# Ejercicio1.net
KiCad netlist of a schematic drawn in Altium Designer
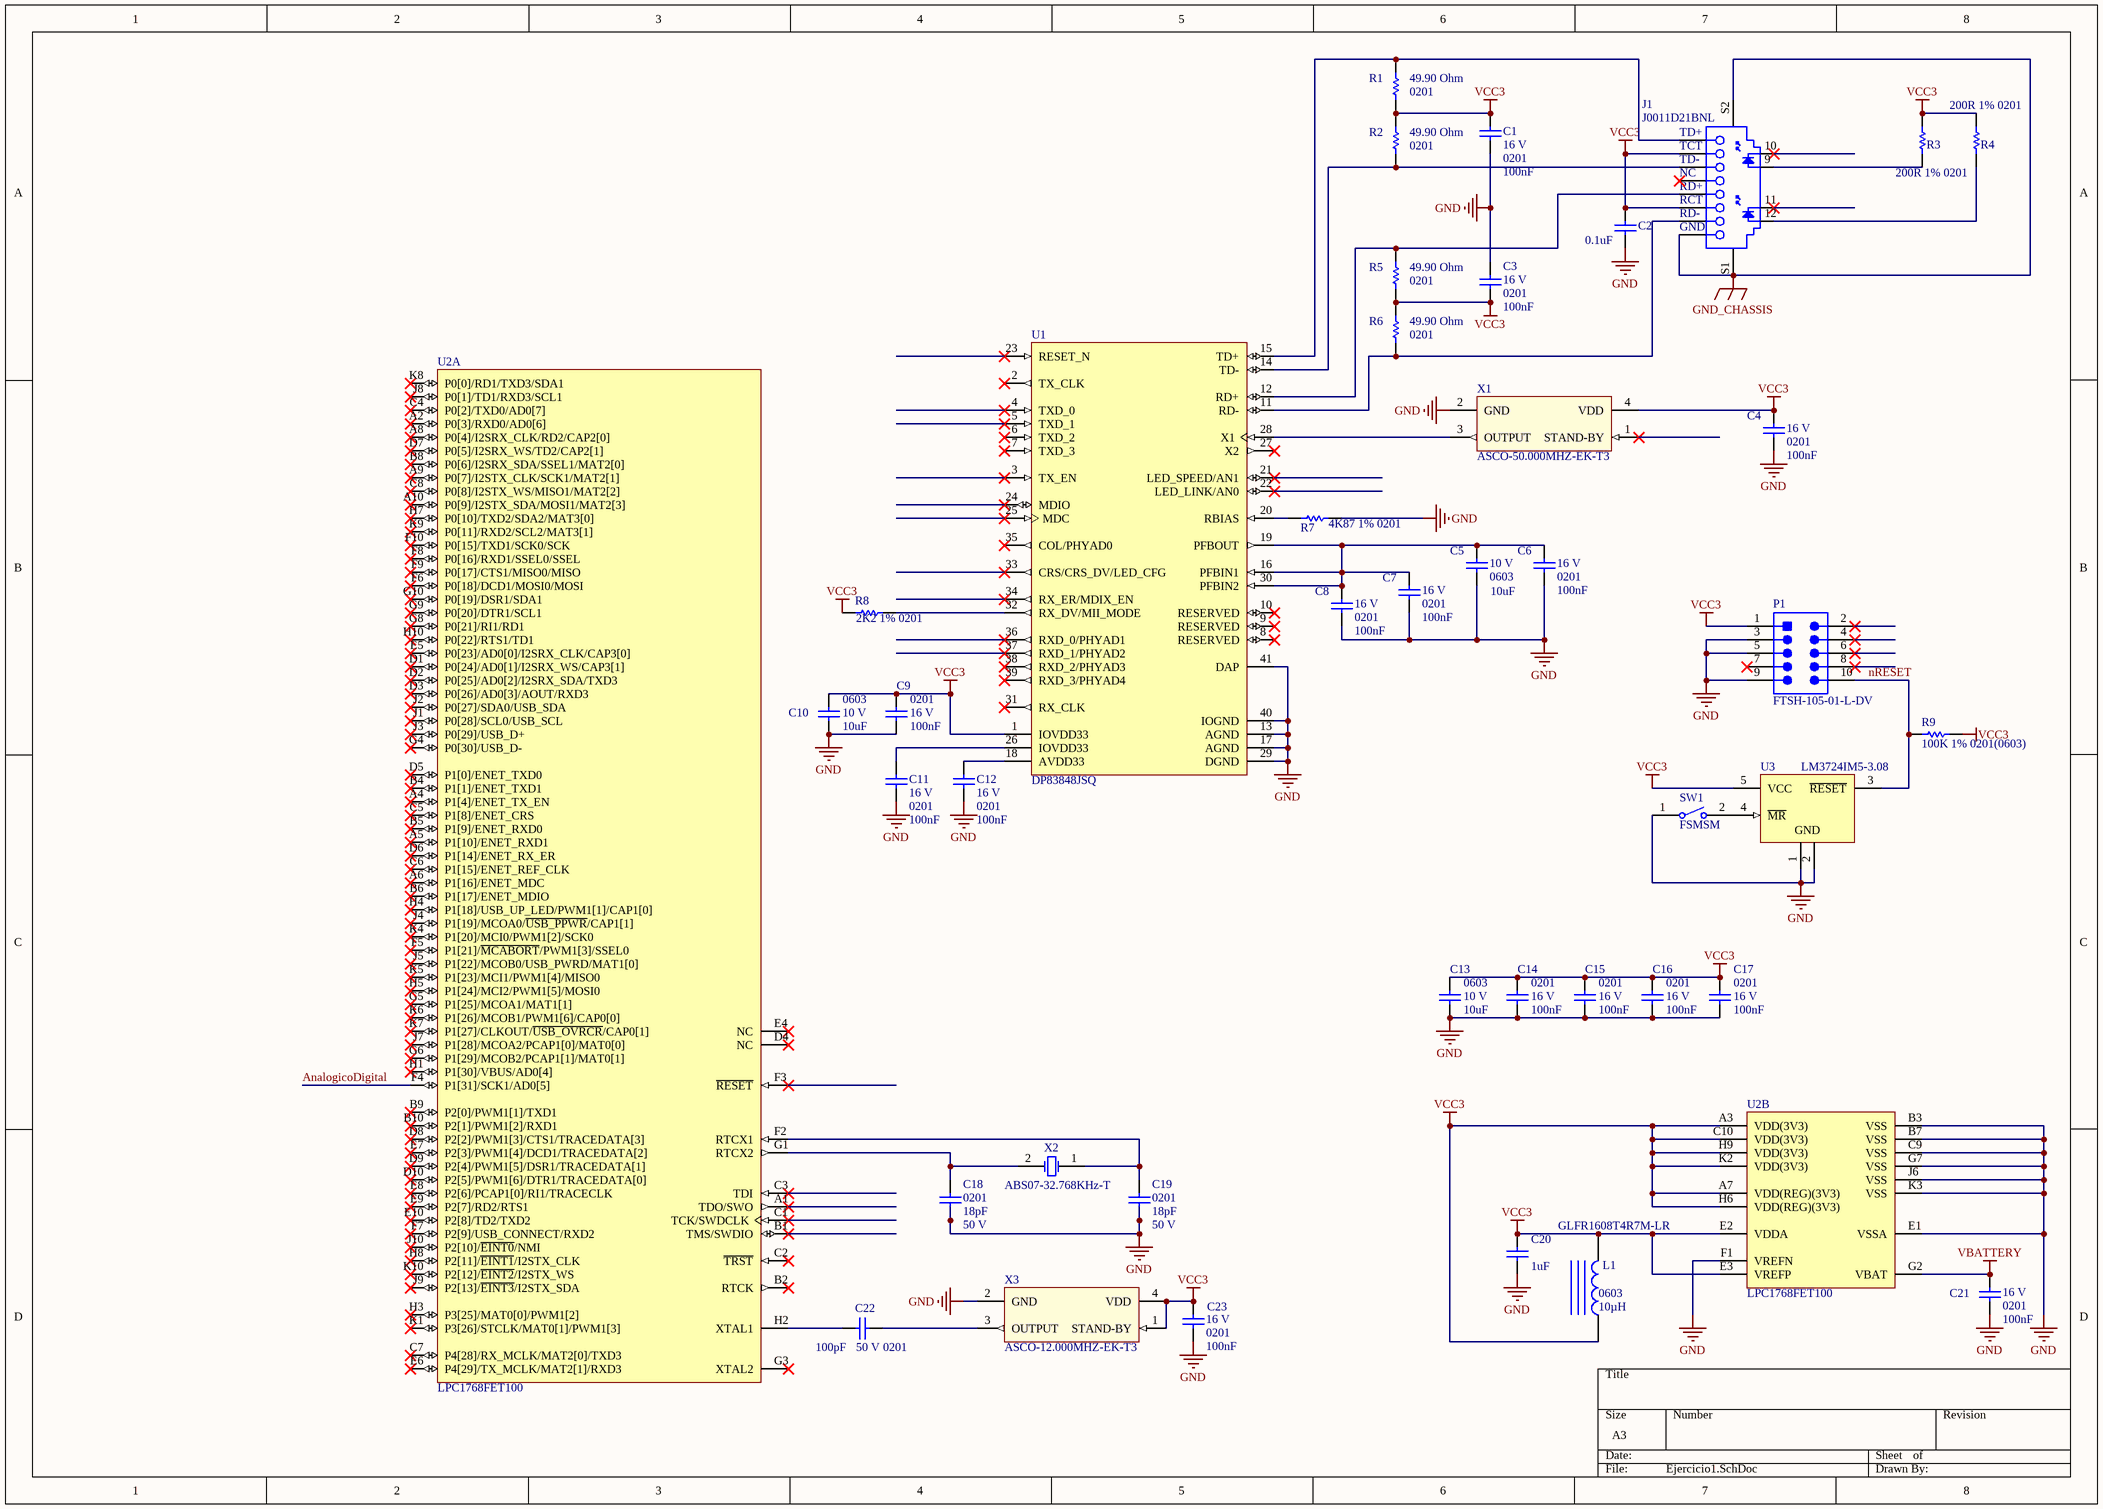
[diagram p0: Ejercicio1.SchDoc]

(export (version "E")
  (design (tool "Eeschema 10.0.6"))
  (components
    (comp (ref "C1")
      (value "100nF")
      (footprint "CAPC0201(0603)33_N")
      (description "CAP 100nF 16V ±10% 0201 (0603 Metric) Thickness 0.33mm SMD")
      (fields
        (field (name "RATED VOLTAGE") "16 V")
        (field (name "TOLERANCE") "Â±10%")
        (field (name "CASE-EIA") "0201")
        (field (name "Comment") "CAP 100nF 16V 0201(0603)")
      )
      (libsource (lib "Altium Content Vault") (part "CMP-1033-00663-1"))
    )
    (comp (ref "C2")
      (value "GRM188R71C104KA01D")
      (footprint "MURA-0603_H_0.9_L")
      (description "CAP, Ceramic, 0.1 uF, 10%, 16 V, 0603, RoHS, Tape and Reel")
      (fields
        (field (name "MANUFACTURER") "Murata")
        (field (name "CAPACITANCE") "0.1uF")
        (field (name "TOLERANCE") "10%")
      )
      (libsource (lib "Altium Content Vault") (part "CMP-2000-05253-1"))
    )
    (comp (ref "C3")
      (value "100nF")
      (footprint "CAPC0201(0603)33_N")
      (description "CAP 100nF 16V ±10% 0201 (0603 Metric) Thickness 0.33mm SMD")
      (fields
        (field (name "RATED VOLTAGE") "16 V")
        (field (name "TOLERANCE") "Â±10%")
        (field (name "CASE-EIA") "0201")
        (field (name "Comment") "CAP 100nF 16V 0201(0603)")
      )
      (libsource (lib "Altium Content Vault") (part "CMP-1033-00663-1"))
    )
    (comp (ref "C4")
      (value "100nF")
      (footprint "CAPC0201(0603)33_N")
      (description "CAP 100nF 16V ±10% 0201 (0603 Metric) Thickness 0.33mm SMD")
      (fields
        (field (name "RATED VOLTAGE") "16 V")
        (field (name "TOLERANCE") "Â±10%")
        (field (name "CASE-EIA") "0201")
        (field (name "Comment") "CAP 100nF 16V 0201(0603)")
      )
      (libsource (lib "Altium Content Vault") (part "CMP-1033-00663-1"))
    )
    (comp (ref "C5")
      (value "10uF")
      (footprint "CAPC0603(1608)100_N")
      (description "CAP 10uF 10V ±10% 0603 (1608 Metric) Thickness 1mm SMD")
      (fields
        (field (name "TOLERANCE") "Â±10%")
        (field (name "RATED VOLTAGE") "10 V")
        (field (name "CASE-EIA") "0603")
        (field (name "Comment") "CAP 10uF 10V 0603(1608)")
      )
      (libsource (lib "Altium Content Vault") (part "CMP-1035-02799-1"))
    )
    (comp (ref "C6")
      (value "100nF")
      (footprint "CAPC0201(0603)33_N")
      (description "CAP 100nF 16V ±10% 0201 (0603 Metric) Thickness 0.33mm SMD")
      (fields
        (field (name "RATED VOLTAGE") "16 V")
        (field (name "TOLERANCE") "Â±10%")
        (field (name "CASE-EIA") "0201")
        (field (name "Comment") "CAP 100nF 16V 0201(0603)")
      )
      (libsource (lib "Altium Content Vault") (part "CMP-1033-00663-1"))
    )
    (comp (ref "C7")
      (value "100nF")
      (footprint "CAPC0201(0603)33_N")
      (description "CAP 100nF 16V ±10% 0201 (0603 Metric) Thickness 0.33mm SMD")
      (fields
        (field (name "RATED VOLTAGE") "16 V")
        (field (name "TOLERANCE") "Â±10%")
        (field (name "CASE-EIA") "0201")
        (field (name "Comment") "CAP 100nF 16V 0201(0603)")
      )
      (libsource (lib "Altium Content Vault") (part "CMP-1033-00663-1"))
    )
    (comp (ref "C8")
      (value "100nF")
      (footprint "CAPC0201(0603)33_N")
      (description "CAP 100nF 16V ±10% 0201 (0603 Metric) Thickness 0.33mm SMD")
      (fields
        (field (name "RATED VOLTAGE") "16 V")
        (field (name "TOLERANCE") "Â±10%")
        (field (name "CASE-EIA") "0201")
        (field (name "Comment") "CAP 100nF 16V 0201(0603)")
      )
      (libsource (lib "Altium Content Vault") (part "CMP-1033-00663-1"))
    )
    (comp (ref "C9")
      (value "100nF")
      (footprint "CAPC0201(0603)33_N")
      (description "CAP 100nF 16V ±10% 0201 (0603 Metric) Thickness 0.33mm SMD")
      (fields
        (field (name "RATED VOLTAGE") "16 V")
        (field (name "TOLERANCE") "Â±10%")
        (field (name "CASE-EIA") "0201")
        (field (name "Comment") "CAP 100nF 16V 0201(0603)")
      )
      (libsource (lib "Altium Content Vault") (part "CMP-1033-00663-1"))
    )
    (comp (ref "C10")
      (value "10uF")
      (footprint "CAPC0603(1608)100_N")
      (description "CAP 10uF 10V ±10% 0603 (1608 Metric) Thickness 1mm SMD")
      (fields
        (field (name "TOLERANCE") "Â±10%")
        (field (name "RATED VOLTAGE") "10 V")
        (field (name "CASE-EIA") "0603")
        (field (name "Comment") "CAP 10uF 10V 0603(1608)")
      )
      (libsource (lib "Altium Content Vault") (part "CMP-1035-02799-1"))
    )
    (comp (ref "C11")
      (value "100nF")
      (footprint "CAPC0201(0603)33_N")
      (description "CAP 100nF 16V ±10% 0201 (0603 Metric) Thickness 0.33mm SMD")
      (fields
        (field (name "RATED VOLTAGE") "16 V")
        (field (name "TOLERANCE") "Â±10%")
        (field (name "CASE-EIA") "0201")
        (field (name "Comment") "CAP 100nF 16V 0201(0603)")
      )
      (libsource (lib "Altium Content Vault") (part "CMP-1033-00663-1"))
    )
    (comp (ref "C12")
      (value "100nF")
      (footprint "CAPC0201(0603)33_N")
      (description "CAP 100nF 16V ±10% 0201 (0603 Metric) Thickness 0.33mm SMD")
      (fields
        (field (name "RATED VOLTAGE") "16 V")
        (field (name "TOLERANCE") "Â±10%")
        (field (name "CASE-EIA") "0201")
        (field (name "Comment") "CAP 100nF 16V 0201(0603)")
      )
      (libsource (lib "Altium Content Vault") (part "CMP-1033-00663-1"))
    )
    (comp (ref "C13")
      (value "10uF")
      (footprint "CAPC0603(1608)100_N")
      (description "CAP 10uF 10V ±10% 0603 (1608 Metric) Thickness 1mm SMD")
      (fields
        (field (name "TOLERANCE") "Â±10%")
        (field (name "RATED VOLTAGE") "10 V")
        (field (name "CASE-EIA") "0603")
        (field (name "Comment") "CAP 10uF 10V 0603(1608)")
      )
      (libsource (lib "Altium Content Vault") (part "CMP-1035-02799-1"))
    )
    (comp (ref "C14")
      (value "100nF")
      (footprint "CAPC0201(0603)33_N")
      (description "CAP 100nF 16V ±10% 0201 (0603 Metric) Thickness 0.33mm SMD")
      (fields
        (field (name "RATED VOLTAGE") "16 V")
        (field (name "TOLERANCE") "Â±10%")
        (field (name "CASE-EIA") "0201")
        (field (name "Comment") "CAP 100nF 16V 0201(0603)")
      )
      (libsource (lib "Altium Content Vault") (part "CMP-1033-00663-1"))
    )
    (comp (ref "C15")
      (value "100nF")
      (footprint "CAPC0201(0603)33_N")
      (description "CAP 100nF 16V ±10% 0201 (0603 Metric) Thickness 0.33mm SMD")
      (fields
        (field (name "RATED VOLTAGE") "16 V")
        (field (name "TOLERANCE") "Â±10%")
        (field (name "CASE-EIA") "0201")
        (field (name "Comment") "CAP 100nF 16V 0201(0603)")
      )
      (libsource (lib "Altium Content Vault") (part "CMP-1033-00663-1"))
    )
    (comp (ref "C16")
      (value "100nF")
      (footprint "CAPC0201(0603)33_N")
      (description "CAP 100nF 16V ±10% 0201 (0603 Metric) Thickness 0.33mm SMD")
      (fields
        (field (name "RATED VOLTAGE") "16 V")
        (field (name "TOLERANCE") "Â±10%")
        (field (name "CASE-EIA") "0201")
        (field (name "Comment") "CAP 100nF 16V 0201(0603)")
      )
      (libsource (lib "Altium Content Vault") (part "CMP-1033-00663-1"))
    )
    (comp (ref "C17")
      (value "100nF")
      (footprint "CAPC0201(0603)33_N")
      (description "CAP 100nF 16V ±10% 0201 (0603 Metric) Thickness 0.33mm SMD")
      (fields
        (field (name "RATED VOLTAGE") "16 V")
        (field (name "TOLERANCE") "Â±10%")
        (field (name "CASE-EIA") "0201")
        (field (name "Comment") "CAP 100nF 16V 0201(0603)")
      )
      (libsource (lib "Altium Content Vault") (part "CMP-1033-00663-1"))
    )
    (comp (ref "C18")
      (value "18pF")
      (footprint "CAPC0201(0603)33_M")
      (description "CAP 18pF 50V ±2% 0201 (0603 Metric) Thickness 0.33mm SMD")
      (fields
        (field (name "CASE-EIA") "0201")
        (field (name "TOLERANCE") "Â±2%")
        (field (name "RATED VOLTAGE") "50 V")
        (field (name "Comment") "CAP 18pF 50V 0201(0603)")
      )
      (libsource (lib "Altium Content Vault") (part "CMP-1033-00395-1"))
    )
    (comp (ref "C19")
      (value "18pF")
      (footprint "CAPC0201(0603)33_M")
      (description "CAP 18pF 50V ±2% 0201 (0603 Metric) Thickness 0.33mm SMD")
      (fields
        (field (name "CASE-EIA") "0201")
        (field (name "TOLERANCE") "Â±2%")
        (field (name "RATED VOLTAGE") "50 V")
        (field (name "Comment") "CAP 18pF 50V 0201(0603)")
      )
      (libsource (lib "Altium Content Vault") (part "CMP-1033-00395-1"))
    )
    (comp (ref "C20")
      (value "1uF")
      (footprint "CAPC0603(1608)100_N")
      (description "CAP 1uF 50V ±20% 0603 (1608 Metric) Thickness 1mm SMD")
      (fields (field (name "TOLERANCE") "Â±20%") (field (name "Comment") "CAP 1uF 50V 0603(1608)"))
      (libsource (lib "Altium Content Vault") (part "CMP-1035-02746-1"))
    )
    (comp (ref "C21")
      (value "100nF")
      (footprint "CAPC0201(0603)33_N")
      (description "CAP 100nF 16V ±10% 0201 (0603 Metric) Thickness 0.33mm SMD")
      (fields
        (field (name "RATED VOLTAGE") "16 V")
        (field (name "TOLERANCE") "Â±10%")
        (field (name "CASE-EIA") "0201")
        (field (name "Comment") "CAP 100nF 16V 0201(0603)")
      )
      (libsource (lib "Altium Content Vault") (part "CMP-1033-00663-1"))
    )
    (comp (ref "C22")
      (value "100pF")
      (footprint "CAPC0201(0603)33_M")
      (description "CAP 100pF 50V ±2% 0201 (0603 Metric) Thickness 0.33mm SMD")
      (fields
        (field (name "RATED VOLTAGE") "50 V")
        (field (name "TOLERANCE") "Â±2%")
        (field (name "CASE-EIA") "0201")
        (field (name "Comment") "CAP 100pF 50V 0201(0603)")
      )
      (libsource (lib "Altium Content Vault") (part "CMP-1033-00496-1"))
    )
    (comp (ref "C23")
      (value "100nF")
      (footprint "CAPC0201(0603)33_N")
      (description "CAP 100nF 16V ±10% 0201 (0603 Metric) Thickness 0.33mm SMD")
      (fields
        (field (name "RATED VOLTAGE") "16 V")
        (field (name "TOLERANCE") "Â±10%")
        (field (name "CASE-EIA") "0201")
        (field (name "Comment") "CAP 100nF 16V 0201(0603)")
      )
      (libsource (lib "Altium Content Vault") (part "CMP-1033-00663-1"))
    )
    (comp (ref "J1")
      (value "J0011D21BNL")
      (footprint "PULS-J00XXD21XNL-B-12")
      (fields (field (name "MANUFACTURER") "Pulse"))
      (libsource (lib "Altium Content Vault") (part "CMP-2000-05321-1"))
    )
    (comp (ref "L1")
      (value "GLFR1608T4R7M-LR")
      (footprint "INDC1608X100X35NL20T15")
      (description "Chip Inductor, 4.7 uH, +/- 20%, -40 to 105 degC, 0603 (1608 Metric), RoHS, Tape and Reel")
      (fields
        (field (name "MANUFACTURER") "TDK")
        (field (name "INDUCTANCE") "10µH")
        (field (name "PACKAGE REFERENCE") "0603")
        (field (name "TOLERANCE") "±20%")
      )
      (libsource (lib "Altium Content Vault") (part "CMP-2000-06322-1"))
    )
    (comp (ref "P1")
      (value "FTSH-105-01-L-DV")
      (footprint "SMTC-FTSH-105-01-L-DV_V")
      (description "Male Header, Pitch 1.27 mm, 2 x 5 Position, Height 5.96 mm, -55 to 125 degC, RoHS, Bulk")
      (fields (field (name "MANUFACTURER") "Samtec"))
      (libsource (lib "Altium Content Vault") (part "CMP-2000-05354-1"))
    )
    (comp (ref "R1")
      (value "49.90 Ohm")
      (footprint "RESC0201(0603)_L")
      (description "49R9 0.05W 1% 0201 (0603 Metric)  SMD")
      (fields
        (field (name "CASE-EIA") "0201")
        (field (name "POWER") "0.05 W")
        (field (name "TOLERANCE") "1 %")
      )
      (libsource (lib "Altium Content Vault") (part "CMP-1010-00269-1"))
    )
    (comp (ref "R2")
      (value "49.90 Ohm")
      (footprint "RESC0201(0603)_L")
      (description "49R9 0.05W 1% 0201 (0603 Metric)  SMD")
      (fields
        (field (name "CASE-EIA") "0201")
        (field (name "POWER") "0.05 W")
        (field (name "TOLERANCE") "1 %")
      )
      (libsource (lib "Altium Content Vault") (part "CMP-1010-00269-1"))
    )
    (comp (ref "R3")
      (value "200R 1% 0201")
      (footprint "RESC0201(0603)_M")
      (description "200R 0.05W 1% 0201 (0603 Metric)  SMD")
      (fields (field (name "POWER") "0.05 W") (field (name "TOLERANCE") "1 %"))
      (libsource (lib "Altium Content Vault") (part "CMP-1010-00335-1"))
    )
    (comp (ref "R4")
      (value "200R 1% 0201")
      (footprint "RESC0201(0603)_M")
      (description "200R 0.05W 1% 0201 (0603 Metric)  SMD")
      (fields (field (name "POWER") "0.05 W") (field (name "TOLERANCE") "1 %"))
      (libsource (lib "Altium Content Vault") (part "CMP-1010-00335-1"))
    )
    (comp (ref "R5")
      (value "49.90 Ohm")
      (footprint "RESC0201(0603)_L")
      (description "49R9 0.05W 1% 0201 (0603 Metric)  SMD")
      (fields
        (field (name "CASE-EIA") "0201")
        (field (name "POWER") "0.05 W")
        (field (name "TOLERANCE") "1 %")
      )
      (libsource (lib "Altium Content Vault") (part "CMP-1010-00269-1"))
    )
    (comp (ref "R6")
      (value "49.90 Ohm")
      (footprint "RESC0201(0603)_L")
      (description "49R9 0.05W 1% 0201 (0603 Metric)  SMD")
      (fields
        (field (name "CASE-EIA") "0201")
        (field (name "POWER") "0.05 W")
        (field (name "TOLERANCE") "1 %")
      )
      (libsource (lib "Altium Content Vault") (part "CMP-1010-00269-1"))
    )
    (comp (ref "R7")
      (value "4K87 1% 0201")
      (footprint "RESC0201(0603)_L")
      (description "4K87 0.05W 1% 0201 (0603 Metric)  SMD")
      (fields (field (name "POWER") "0.05 W") (field (name "TOLERANCE") "1 %"))
      (libsource (lib "Altium Content Vault") (part "CMP-1010-00494-1"))
    )
    (comp (ref "R8")
      (value "2K2 1% 0201")
      (footprint "RESC0201(0603)_N")
      (description "2K2 0.05W 1% 0201 (0603 Metric)  SMD")
      (fields (field (name "TOLERANCE") "1 %") (field (name "POWER") "0.05 W"))
      (libsource (lib "Altium Content Vault") (part "CMP-1010-00452-1"))
    )
    (comp (ref "R9")
      (value "100K 1% 0201(0603)")
      (footprint "RESC0201(0603)_L")
      (description "22K 0.05W 1% 0201 (0603 Metric)  SMD")
      (fields (field (name "POWER") "0.05 W") (field (name "TOLERANCE") "1 %"))
      (libsource (lib "Altium Content Vault") (part "CMP-1010-00565-1"))
    )
    (comp (ref "SW1")
      (value "FSMSM")
      (footprint "TECO-FSMSM-2_V")
      (description "FSMSM Push Button Switch, 50 mA, -35 to 85 degC, 2-Pin SMD, RoHS, Bulk")
      (fields (field (name "MANUFACTURER") "TE Connectivity"))
      (libsource (lib "Altium Content Vault") (part "CMP-2000-07511-1"))
    )
    (comp (ref "U1")
      (value "DP83848JSQ")
      (footprint "SQA40B")
      (description "PHYTER® Mini LS Commercial Temperature Single Port 10/100 Mb/s Ethernet Transceiver, 40-pin LLP")
      (fields (field (name "MANUFACTURER") "National Semiconductor"))
      (libsource (lib "Altium Content Vault") (part "CMP-0058-00374-3"))
    )
    (comp (ref "U2")
      (value "LPC1768FET100")
      (footprint "SOT926-1")
      (libsource (lib "Altium Content Vault") (part "CMP-0174-00003-3"))
    )
    (comp (ref "U3")
      (value "LM3724IM5-3.08")
      (footprint "MF05A_N")
      (description "Microprocessor Reset Circuits, 5-pin SOT-23")
      (fields (field (name "MANUFACTURER") "National Semiconductor"))
      (libsource (lib "Altium Content Vault") (part "CMP-0063-01084-2"))
    )
    (comp (ref "X1")
      (value "ASCO-50.000MHZ-EK-T3")
      (footprint "ABRA-ASCO-50.000MHZ-EK-T3-4_V")
      (description "Crystal Clock Oscillator, 50 MHz, -20 to 70 degC, 1.6 x 1.2 x 0.7 mm SMD")
      (fields (field (name "MANUFACTURER") "Abracon"))
      (libsource (lib "Altium Content Vault") (part "CMP-0461-00001-3"))
    )
    (comp (ref "X2")
      (value "ABS07-32.768KHz-T")
      (footprint "ABRA-ABS07-2_V")
      (description "Crystal, 32.768 kHz, 12.5 pF, -40 to 85 degC, SMD Low Profile 3.2 x 1.5 x 0.9 mm, Tape and Reel")
      (fields (field (name "MANUFACTURER") "Abracon"))
      (libsource (lib "Altium Content Vault") (part "CMP-0447-00001-2"))
    )
    (comp (ref "X3")
      (value "ASCO-12.000MHZ-EK-T3")
      (footprint "ABRA-ASCO-50.000MHZ-EK-T3-4_V")
      (description "Crystal Clock Oscillator, 50 MHz, -20 to 70 degC, 1.6 x 1.2 x 0.7 mm SMD")
      (fields (field (name "MANUFACTURER") "Abracon") (field (name "PARTNUMBER") "ASCO-50.000MHZ-EK-T3"))
      (libsource (lib "Altium Content Vault") (part "CMP-0461-00001-3"))
    )
  )
  (nets
    (net (code "1") (name "/AnalogicoDigital") (class "Default")
      (node (ref "U2") (pin "F4") (pinfunction "P1[31]/SCK1/AD0[5]_F4") (pintype "bidirectional"))
    )
    (net (code "2") (name "/nRESET") (class "Default")
      (node (ref "P1") (pin "10") (pinfunction "10_10") (pintype "passive"))
      (node (ref "R9") (pin "2") (pinfunction "2_2") (pintype "passive"))
      (node (ref "U3") (pin "3") (pinfunction "~{RESET}_3") (pintype "open_collector"))
    )
    (net (code "3") (name "GND") (class "Default")
      (node (ref "C1") (pin "2") (pinfunction "2_2") (pintype "passive"))
      (node (ref "C10") (pin "1") (pinfunction "1_1") (pintype "passive"))
      (node (ref "C11") (pin "2") (pinfunction "2_2") (pintype "passive"))
      (node (ref "C12") (pin "2") (pinfunction "2_2") (pintype "passive"))
      (node (ref "C13") (pin "1") (pinfunction "1_1") (pintype "passive"))
      (node (ref "C14") (pin "1") (pinfunction "1_1") (pintype "passive"))
      (node (ref "C15") (pin "1") (pinfunction "1_1") (pintype "passive"))
      (node (ref "C16") (pin "1") (pinfunction "1_1") (pintype "passive"))
      (node (ref "C17") (pin "1") (pinfunction "1_1") (pintype "passive"))
      (node (ref "C18") (pin "1") (pinfunction "1_1") (pintype "passive"))
      (node (ref "C19") (pin "1") (pinfunction "1_1") (pintype "passive"))
      (node (ref "C2") (pin "1") (pinfunction "1_1") (pintype "passive"))
      (node (ref "C20") (pin "1") (pinfunction "1_1") (pintype "passive"))
      (node (ref "C21") (pin "2") (pinfunction "2_2") (pintype "passive"))
      (node (ref "C23") (pin "2") (pinfunction "2_2") (pintype "passive"))
      (node (ref "C3") (pin "1") (pinfunction "1_1") (pintype "passive"))
      (node (ref "C4") (pin "2") (pinfunction "2_2") (pintype "passive"))
      (node (ref "C5") (pin "2") (pinfunction "2_2") (pintype "passive"))
      (node (ref "C6") (pin "2") (pinfunction "2_2") (pintype "passive"))
      (node (ref "C7") (pin "2") (pinfunction "2_2") (pintype "passive"))
      (node (ref "C8") (pin "2") (pinfunction "2_2") (pintype "passive"))
      (node (ref "C9") (pin "1") (pinfunction "1_1") (pintype "passive"))
      (node (ref "P1") (pin "3") (pinfunction "3_3") (pintype "passive"))
      (node (ref "P1") (pin "5") (pinfunction "5_5") (pintype "passive"))
      (node (ref "P1") (pin "9") (pinfunction "9_9") (pintype "passive"))
      (node (ref "R7") (pin "2") (pinfunction "2_2") (pintype "passive"))
      (node (ref "SW1") (pin "1") (pinfunction "1_1") (pintype "passive"))
      (node (ref "U1") (pin "13") (pinfunction "AGND_13") (pintype "power_in"))
      (node (ref "U1") (pin "17") (pinfunction "AGND_17") (pintype "power_in"))
      (node (ref "U1") (pin "29") (pinfunction "DGND_29") (pintype "power_in"))
      (node (ref "U1") (pin "40") (pinfunction "IOGND_40") (pintype "power_in"))
      (node (ref "U1") (pin "41") (pinfunction "DAP_41") (pintype "passive"))
      (node (ref "U2") (pin "B3") (pinfunction "VSS_B3") (pintype "power_in"))
      (node (ref "U2") (pin "B7") (pinfunction "VSS_B7") (pintype "power_in"))
      (node (ref "U2") (pin "C9") (pinfunction "VSS_C9") (pintype "power_in"))
      (node (ref "U2") (pin "E1") (pinfunction "VSSA_E1") (pintype "power_in"))
      (node (ref "U2") (pin "F1") (pinfunction "VREFN_F1") (pintype "power_in"))
      (node (ref "U2") (pin "G7") (pinfunction "VSS_G7") (pintype "power_in"))
      (node (ref "U2") (pin "J6") (pinfunction "VSS_J6") (pintype "power_in"))
      (node (ref "U2") (pin "K3") (pinfunction "VSS_K3") (pintype "power_in"))
      (node (ref "U3") (pin "1") (pinfunction "GND_1") (pintype "power_in"))
      (node (ref "U3") (pin "2") (pinfunction "GND_2") (pintype "power_in"))
      (node (ref "X1") (pin "2") (pinfunction "GND_2") (pintype "power_in"))
      (node (ref "X3") (pin "2") (pinfunction "GND_2") (pintype "power_in"))
    )
    (net (code "4") (name "GND_CHASSIS") (class "Default")
      (node (ref "J1") (pin "8") (pinfunction "CHS_GROUND_8") (pintype "passive"))
      (node (ref "J1") (pin "S1") (pinfunction "S1_S1") (pintype "passive"))
      (node (ref "J1") (pin "S2") (pinfunction "S2_S2") (pintype "passive"))
    )
    (net (code "5") (name "Net-(C11-Pad1)") (class "Default")
      (node (ref "C11") (pin "1") (pinfunction "1_1") (pintype "passive"))
      (node (ref "U1") (pin "26") (pinfunction "IOVDD33_26") (pintype "power_in"))
    )
    (net (code "6") (name "Net-(J1-Pad9)") (class "Default")
      (node (ref "J1") (pin "9") (pinfunction "9_9") (pintype "passive"))
      (node (ref "R3") (pin "1") (pinfunction "1_1") (pintype "passive"))
    )
    (net (code "7") (name "Net-(J1-Pad12)") (class "Default")
      (node (ref "J1") (pin "12") (pinfunction "12_12") (pintype "passive"))
      (node (ref "R4") (pin "1") (pinfunction "1_1") (pintype "passive"))
    )
    (net (code "8") (name "Net-(J1-RD+)") (class "Default")
      (node (ref "J1") (pin "3") (pinfunction "RD+_3") (pintype "passive"))
      (node (ref "R5") (pin "2") (pinfunction "2_2") (pintype "passive"))
      (node (ref "U1") (pin "12") (pinfunction "RD+_12") (pintype "bidirectional"))
    )
    (net (code "9") (name "Net-(J1-RD-)") (class "Default")
      (node (ref "J1") (pin "6") (pinfunction "RD-_6") (pintype "passive"))
      (node (ref "R6") (pin "1") (pinfunction "1_1") (pintype "passive"))
      (node (ref "U1") (pin "11") (pinfunction "RD-_11") (pintype "bidirectional"))
    )
    (net (code "10") (name "Net-(J1-TD+)") (class "Default")
      (node (ref "J1") (pin "1") (pinfunction "TD+_1") (pintype "passive"))
      (node (ref "R1") (pin "2") (pinfunction "2_2") (pintype "passive"))
      (node (ref "U1") (pin "15") (pinfunction "TD+_15") (pintype "bidirectional"))
    )
    (net (code "11") (name "Net-(J1-TD-)") (class "Default")
      (node (ref "J1") (pin "2") (pinfunction "TD-_2") (pintype "passive"))
      (node (ref "R2") (pin "1") (pinfunction "1_1") (pintype "passive"))
      (node (ref "U1") (pin "14") (pinfunction "TD-_14") (pintype "bidirectional"))
    )
    (net (code "12") (name "Net-(U1-AVDD33)") (class "Default")
      (node (ref "C12") (pin "1") (pinfunction "1_1") (pintype "passive"))
      (node (ref "U1") (pin "18") (pinfunction "AVDD33_18") (pintype "power_in"))
    )
    (net (code "13") (name "Net-(U1-PFBIN1)") (class "Default")
      (node (ref "C5") (pin "1") (pinfunction "1_1") (pintype "passive"))
      (node (ref "C6") (pin "1") (pinfunction "1_1") (pintype "passive"))
      (node (ref "C7") (pin "1") (pinfunction "1_1") (pintype "passive"))
      (node (ref "C8") (pin "1") (pinfunction "1_1") (pintype "passive"))
      (node (ref "U1") (pin "16") (pinfunction "PFBIN1_16") (pintype "input"))
      (node (ref "U1") (pin "19") (pinfunction "PFBOUT_19") (pintype "output"))
      (node (ref "U1") (pin "30") (pinfunction "PFBIN2_30") (pintype "input"))
    )
    (net (code "14") (name "Net-(U1-RBIAS)") (class "Default")
      (node (ref "R7") (pin "1") (pinfunction "1_1") (pintype "passive"))
      (node (ref "U1") (pin "20") (pinfunction "RBIAS_20") (pintype "input"))
    )
    (net (code "15") (name "Net-(U1-RX_DV{slash}MII_MODE)") (class "Default")
      (node (ref "R8") (pin "1") (pinfunction "1_1") (pintype "passive"))
      (node (ref "U1") (pin "32") (pinfunction "RX_DV/MII_MODE_32") (pintype "output"))
    )
    (net (code "16") (name "Net-(U1-X1)") (class "Default")
      (node (ref "U1") (pin "28") (pinfunction "X1_28") (pintype "input"))
      (node (ref "X1") (pin "3") (pinfunction "OUTPUT_3") (pintype "output"))
    )
    (net (code "17") (name "Net-(U2A-RTCX1)") (class "Default")
      (node (ref "C19") (pin "2") (pinfunction "2_2") (pintype "passive"))
      (node (ref "U2") (pin "F2") (pinfunction "RTCX1_F2") (pintype "input"))
      (node (ref "X2") (pin "1") (pinfunction "X1_1") (pintype "passive"))
    )
    (net (code "18") (name "Net-(U2A-RTCX2)") (class "Default")
      (node (ref "C18") (pin "2") (pinfunction "2_2") (pintype "passive"))
      (node (ref "U2") (pin "G1") (pinfunction "RTCX2_G1") (pintype "output"))
      (node (ref "X2") (pin "2") (pinfunction "X2_2") (pintype "passive"))
    )
    (net (code "19") (name "Net-(U2A-XTAL1)") (class "Default")
      (node (ref "C22") (pin "2") (pinfunction "2_2") (pintype "passive"))
      (node (ref "U2") (pin "H2") (pinfunction "XTAL1_H2") (pintype "passive"))
    )
    (net (code "20") (name "Net-(U3-~{MR})") (class "Default")
      (node (ref "SW1") (pin "2") (pinfunction "2_2") (pintype "passive"))
      (node (ref "U3") (pin "4") (pinfunction "~{MR}_4") (pintype "input"))
    )
    (net (code "21") (name "Net-(X3-OUTPUT)") (class "Default")
      (node (ref "C22") (pin "1") (pinfunction "1_1") (pintype "passive"))
      (node (ref "X3") (pin "3") (pinfunction "OUTPUT_3") (pintype "output"))
    )
    (net (code "22") (name "VBATTERY") (class "Default")
      (node (ref "C21") (pin "1") (pinfunction "1_1") (pintype "passive"))
      (node (ref "U2") (pin "G2") (pinfunction "VBAT_G2") (pintype "power_in"))
    )
    (net (code "23") (name "VCC3") (class "Default")
      (node (ref "C1") (pin "1") (pinfunction "1_1") (pintype "passive"))
      (node (ref "C10") (pin "2") (pinfunction "2_2") (pintype "passive"))
      (node (ref "C13") (pin "2") (pinfunction "2_2") (pintype "passive"))
      (node (ref "C14") (pin "2") (pinfunction "2_2") (pintype "passive"))
      (node (ref "C15") (pin "2") (pinfunction "2_2") (pintype "passive"))
      (node (ref "C16") (pin "2") (pinfunction "2_2") (pintype "passive"))
      (node (ref "C17") (pin "2") (pinfunction "2_2") (pintype "passive"))
      (node (ref "C2") (pin "2") (pinfunction "2_2") (pintype "passive"))
      (node (ref "C20") (pin "2") (pinfunction "2_2") (pintype "passive"))
      (node (ref "C23") (pin "1") (pinfunction "1_1") (pintype "passive"))
      (node (ref "C3") (pin "2") (pinfunction "2_2") (pintype "passive"))
      (node (ref "C4") (pin "1") (pinfunction "1_1") (pintype "passive"))
      (node (ref "C9") (pin "2") (pinfunction "2_2") (pintype "passive"))
      (node (ref "J1") (pin "4") (pinfunction "TCT_4") (pintype "passive"))
      (node (ref "J1") (pin "5") (pinfunction "RCT_5") (pintype "passive"))
      (node (ref "L1") (pin "1") (pinfunction "1_1") (pintype "passive"))
      (node (ref "L1") (pin "2") (pinfunction "2_2") (pintype "passive"))
      (node (ref "P1") (pin "1") (pinfunction "1_1") (pintype "passive"))
      (node (ref "R1") (pin "1") (pinfunction "1_1") (pintype "passive"))
      (node (ref "R2") (pin "2") (pinfunction "2_2") (pintype "passive"))
      (node (ref "R3") (pin "2") (pinfunction "2_2") (pintype "passive"))
      (node (ref "R4") (pin "2") (pinfunction "2_2") (pintype "passive"))
      (node (ref "R5") (pin "1") (pinfunction "1_1") (pintype "passive"))
      (node (ref "R6") (pin "2") (pinfunction "2_2") (pintype "passive"))
      (node (ref "R8") (pin "2") (pinfunction "2_2") (pintype "passive"))
      (node (ref "R9") (pin "1") (pinfunction "1_1") (pintype "passive"))
      (node (ref "U1") (pin "1") (pinfunction "IOVDD33_1") (pintype "power_in"))
      (node (ref "U2") (pin "A3") (pinfunction "VDD(3V3)_A3") (pintype "power_in"))
      (node (ref "U2") (pin "A7") (pinfunction "VDD(REG)(3V3)_A7") (pintype "power_in"))
      (node (ref "U2") (pin "C10") (pinfunction "VDD(3V3)_C10") (pintype "power_in"))
      (node (ref "U2") (pin "E2") (pinfunction "VDDA_E2") (pintype "power_in"))
      (node (ref "U2") (pin "E3") (pinfunction "VREFP_E3") (pintype "power_in"))
      (node (ref "U2") (pin "H6") (pinfunction "VDD(REG)(3V3)_H6") (pintype "power_in"))
      (node (ref "U2") (pin "H9") (pinfunction "VDD(3V3)_H9") (pintype "power_in"))
      (node (ref "U2") (pin "K2") (pinfunction "VDD(3V3)_K2") (pintype "power_in"))
      (node (ref "U3") (pin "5") (pinfunction "VCC_5") (pintype "power_in"))
      (node (ref "X1") (pin "4") (pinfunction "VDD_4") (pintype "power_in"))
      (node (ref "X3") (pin "1") (pinfunction "STAND-BY_1") (pintype "input"))
      (node (ref "X3") (pin "4") (pinfunction "VDD_4") (pintype "power_in"))
    )
    (net (code "24") (name "unconnected-(J1-NC-Pad7)") (class "Default")
      (node (ref "J1") (pin "7") (pinfunction "NC_7") (pintype "passive+no_connect"))
    )
    (net (code "25") (name "unconnected-(J1-Pad10)") (class "Default")
      (node (ref "J1") (pin "10") (pinfunction "10_10") (pintype "passive+no_connect"))
    )
    (net (code "26") (name "unconnected-(J1-Pad11)") (class "Default")
      (node (ref "J1") (pin "11") (pinfunction "11_11") (pintype "passive+no_connect"))
    )
    (net (code "27") (name "unconnected-(P1-Pad2)") (class "Default")
      (node (ref "P1") (pin "2") (pinfunction "2_2") (pintype "passive+no_connect"))
    )
    (net (code "28") (name "unconnected-(P1-Pad4)") (class "Default")
      (node (ref "P1") (pin "4") (pinfunction "4_4") (pintype "passive+no_connect"))
    )
    (net (code "29") (name "unconnected-(P1-Pad6)") (class "Default")
      (node (ref "P1") (pin "6") (pinfunction "6_6") (pintype "passive+no_connect"))
    )
    (net (code "30") (name "unconnected-(P1-Pad7)") (class "Default")
      (node (ref "P1") (pin "7") (pinfunction "7_7") (pintype "passive+no_connect"))
    )
    (net (code "31") (name "unconnected-(P1-Pad8)") (class "Default")
      (node (ref "P1") (pin "8") (pinfunction "8_8") (pintype "passive+no_connect"))
    )
    (net (code "32") (name "unconnected-(U1-COL{slash}PHYAD0-Pad35)") (class "Default")
      (node (ref "U1") (pin "35") (pinfunction "COL/PHYAD0_35") (pintype "output+no_connect"))
    )
    (net (code "33") (name "unconnected-(U1-CRS{slash}CRS_DV{slash}LED_CFG-Pad33)") (class "Default")
      (node (ref "U1") (pin "33") (pinfunction "CRS/CRS_DV/LED_CFG_33") (pintype "output+no_connect"))
    )
    (net (code "34") (name "unconnected-(U1-LED_LINK{slash}AN0-Pad22)") (class "Default")
      (node (ref "U1") (pin "22") (pinfunction "LED_LINK/AN0_22") (pintype "bidirectional+no_connect"))
    )
    (net (code "35") (name "unconnected-(U1-LED_SPEED{slash}AN1-Pad21)") (class "Default")
      (node (ref "U1") (pin "21") (pinfunction "LED_SPEED/AN1_21") (pintype "bidirectional+no_connect"))
    )
    (net (code "36") (name "unconnected-(U1-MDC-Pad25)") (class "Default")
      (node (ref "U1") (pin "25") (pinfunction "MDC_25") (pintype "input+no_connect"))
    )
    (net (code "37") (name "unconnected-(U1-MDIO-Pad24)") (class "Default")
      (node (ref "U1") (pin "24") (pinfunction "MDIO_24") (pintype "bidirectional+no_connect"))
    )
    (net (code "38") (name "unconnected-(U1-RESERVED-Pad8)") (class "Default")
      (node (ref "U1") (pin "8") (pinfunction "RESERVED_8") (pintype "bidirectional+no_connect"))
    )
    (net (code "39") (name "unconnected-(U1-RESERVED-Pad9)") (class "Default")
      (node (ref "U1") (pin "9") (pinfunction "RESERVED_9") (pintype "bidirectional+no_connect"))
    )
    (net (code "40") (name "unconnected-(U1-RESERVED-Pad10)") (class "Default")
      (node (ref "U1") (pin "10") (pinfunction "RESERVED_10") (pintype "bidirectional+no_connect"))
    )
    (net (code "41") (name "unconnected-(U1-RESET_N-Pad23)") (class "Default")
      (node (ref "U1") (pin "23") (pinfunction "RESET_N_23") (pintype "input+no_connect"))
    )
    (net (code "42") (name "unconnected-(U1-RXD_0{slash}PHYAD1-Pad36)") (class "Default")
      (node (ref "U1") (pin "36") (pinfunction "RXD_0/PHYAD1_36") (pintype "output+no_connect"))
    )
    (net (code "43") (name "unconnected-(U1-RXD_1{slash}PHYAD2-Pad37)") (class "Default")
      (node (ref "U1") (pin "37") (pinfunction "RXD_1/PHYAD2_37") (pintype "output+no_connect"))
    )
    (net (code "44") (name "unconnected-(U1-RXD_2{slash}PHYAD3-Pad38)") (class "Default")
      (node (ref "U1") (pin "38") (pinfunction "RXD_2/PHYAD3_38") (pintype "output+no_connect"))
    )
    (net (code "45") (name "unconnected-(U1-RXD_3{slash}PHYAD4-Pad39)") (class "Default")
      (node (ref "U1") (pin "39") (pinfunction "RXD_3/PHYAD4_39") (pintype "output+no_connect"))
    )
    (net (code "46") (name "unconnected-(U1-RX_CLK-Pad31)") (class "Default")
      (node (ref "U1") (pin "31") (pinfunction "RX_CLK_31") (pintype "output+no_connect"))
    )
    (net (code "47") (name "unconnected-(U1-RX_ER{slash}MDIX_EN-Pad34)") (class "Default")
      (node (ref "U1") (pin "34") (pinfunction "RX_ER/MDIX_EN_34") (pintype "output+no_connect"))
    )
    (net (code "48") (name "unconnected-(U1-TXD_0-Pad4)") (class "Default")
      (node (ref "U1") (pin "4") (pinfunction "TXD_0_4") (pintype "input+no_connect"))
    )
    (net (code "49") (name "unconnected-(U1-TXD_1-Pad5)") (class "Default")
      (node (ref "U1") (pin "5") (pinfunction "TXD_1_5") (pintype "input+no_connect"))
    )
    (net (code "50") (name "unconnected-(U1-TXD_2-Pad6)") (class "Default")
      (node (ref "U1") (pin "6") (pinfunction "TXD_2_6") (pintype "input+no_connect"))
    )
    (net (code "51") (name "unconnected-(U1-TXD_3-Pad7)") (class "Default")
      (node (ref "U1") (pin "7") (pinfunction "TXD_3_7") (pintype "input+no_connect"))
    )
    (net (code "52") (name "unconnected-(U1-TX_CLK-Pad2)") (class "Default")
      (node (ref "U1") (pin "2") (pinfunction "TX_CLK_2") (pintype "output+no_connect"))
    )
    (net (code "53") (name "unconnected-(U1-TX_EN-Pad3)") (class "Default")
      (node (ref "U1") (pin "3") (pinfunction "TX_EN_3") (pintype "input+no_connect"))
    )
    (net (code "54") (name "unconnected-(U1-X2-Pad27)") (class "Default")
      (node (ref "U1") (pin "27") (pinfunction "X2_27") (pintype "output+no_connect"))
    )
    (net (code "55") (name "unconnected-(U2A-NC-PadD4)") (class "Default")
      (node (ref "U2") (pin "D4") (pinfunction "NC_D4") (pintype "passive+no_connect"))
    )
    (net (code "56") (name "unconnected-(U2A-NC-PadE4)") (class "Default")
      (node (ref "U2") (pin "E4") (pinfunction "NC_E4") (pintype "passive+no_connect"))
    )
    (net (code "57") (name "unconnected-(U2A-P0[0]{slash}RD1{slash}TXD3{slash}SDA1-PadK8)") (class "Default")
      (node (ref "U2") (pin "K8") (pinfunction "P0[0]/RD1/TXD3/SDA1_K8") (pintype "bidirectional+no_connect"))
    )
    (net (code "58") (name "unconnected-(U2A-P0[1]{slash}TD1{slash}RXD3{slash}SCL1-PadJ8)") (class "Default")
      (node (ref "U2") (pin "J8") (pinfunction "P0[1]/TD1/RXD3/SCL1_J8") (pintype "bidirectional+no_connect"))
    )
    (net (code "59") (name "unconnected-(U2A-P0[2]{slash}TXD0{slash}AD0[7]-PadC4)") (class "Default")
      (node (ref "U2") (pin "C4") (pinfunction "P0[2]/TXD0/AD0[7]_C4") (pintype "bidirectional+no_connect"))
    )
    (net (code "60") (name "unconnected-(U2A-P0[3]{slash}RXD0{slash}AD0[6]-PadA2)") (class "Default")
      (node (ref "U2") (pin "A2") (pinfunction "P0[3]/RXD0/AD0[6]_A2") (pintype "bidirectional+no_connect"))
    )
    (net (code "61") (name "unconnected-(U2A-P0[4]{slash}I2SRX_CLK{slash}RD2{slash}CAP2[0]-PadA8)") (class "Default")
      (node (ref "U2") (pin "A8") (pinfunction "P0[4]/I2SRX_CLK/RD2/CAP2[0]_A8") (pintype "bidirectional+no_connect"))
    )
    (net (code "62") (name "unconnected-(U2A-P0[5]{slash}I2SRX_WS{slash}TD2{slash}CAP2[1]-PadD7)") (class "Default")
      (node (ref "U2") (pin "D7") (pinfunction "P0[5]/I2SRX_WS/TD2/CAP2[1]_D7") (pintype "bidirectional+no_connect"))
    )
    (net (code "63") (name "unconnected-(U2A-P0[6]{slash}I2SRX_SDA{slash}SSEL1{slash}MAT2[0]-PadB8)") (class "Default")
      (node (ref "U2") (pin "B8") (pinfunction "P0[6]/I2SRX_SDA/SSEL1/MAT2[0]_B8") (pintype "bidirectional+no_connect"))
    )
    (net (code "64") (name "unconnected-(U2A-P0[7]{slash}I2STX_CLK{slash}SCK1{slash}MAT2[1]-PadA9)") (class "Default")
      (node (ref "U2") (pin "A9") (pinfunction "P0[7]/I2STX_CLK/SCK1/MAT2[1]_A9") (pintype "bidirectional+no_connect"))
    )
    (net (code "65") (name "unconnected-(U2A-P0[8]{slash}I2STX_WS{slash}MISO1{slash}MAT2[2]-PadC8)") (class "Default")
      (node (ref "U2") (pin "C8") (pinfunction "P0[8]/I2STX_WS/MISO1/MAT2[2]_C8") (pintype "bidirectional+no_connect"))
    )
    (net (code "66") (name "unconnected-(U2A-P0[9]{slash}I2STX_SDA{slash}MOSI1{slash}MAT2[3]-PadA10)") (class "Default")
      (node (ref "U2") (pin "A10") (pinfunction "P0[9]/I2STX_SDA/MOSI1/MAT2[3]_A10") (pintype "bidirectional+no_connect"))
    )
    (net (code "67") (name "unconnected-(U2A-P0[10]{slash}TXD2{slash}SDA2{slash}MAT3[0]-PadH7)") (class "Default")
      (node (ref "U2") (pin "H7") (pinfunction "P0[10]/TXD2/SDA2/MAT3[0]_H7") (pintype "bidirectional+no_connect"))
    )
    (net (code "68") (name "unconnected-(U2A-P0[11]{slash}RXD2{slash}SCL2{slash}MAT3[1]-PadK9)") (class "Default")
      (node (ref "U2") (pin "K9") (pinfunction "P0[11]/RXD2/SCL2/MAT3[1]_K9") (pintype "bidirectional+no_connect"))
    )
    (net (code "69") (name "unconnected-(U2A-P0[15]{slash}TXD1{slash}SCK0{slash}SCK-PadF10)") (class "Default")
      (node (ref "U2") (pin "F10") (pinfunction "P0[15]/TXD1/SCK0/SCK_F10") (pintype "bidirectional+no_connect"))
    )
    (net (code "70") (name "unconnected-(U2A-P0[16]{slash}RXD1{slash}SSEL0{slash}SSEL-PadF8)") (class "Default")
      (node (ref "U2") (pin "F8") (pinfunction "P0[16]/RXD1/SSEL0/SSEL_F8") (pintype "bidirectional+no_connect"))
    )
    (net (code "71") (name "unconnected-(U2A-P0[17]{slash}CTS1{slash}MISO0{slash}MISO-PadF9)") (class "Default")
      (node (ref "U2") (pin "F9") (pinfunction "P0[17]/CTS1/MISO0/MISO_F9") (pintype "bidirectional+no_connect"))
    )
    (net (code "72") (name "unconnected-(U2A-P0[18]{slash}DCD1{slash}MOSI0{slash}MOSI-PadF6)") (class "Default")
      (node (ref "U2") (pin "F6") (pinfunction "P0[18]/DCD1/MOSI0/MOSI_F6") (pintype "bidirectional+no_connect"))
    )
    (net (code "73") (name "unconnected-(U2A-P0[19]{slash}DSR1{slash}SDA1-PadG10)") (class "Default")
      (node (ref "U2") (pin "G10") (pinfunction "P0[19]/DSR1/SDA1_G10") (pintype "bidirectional+no_connect"))
    )
    (net (code "74") (name "unconnected-(U2A-P0[20]{slash}DTR1{slash}SCL1-PadG9)") (class "Default")
      (node (ref "U2") (pin "G9") (pinfunction "P0[20]/DTR1/SCL1_G9") (pintype "bidirectional+no_connect"))
    )
    (net (code "75") (name "unconnected-(U2A-P0[21]{slash}RI1{slash}RD1-PadG8)") (class "Default")
      (node (ref "U2") (pin "G8") (pinfunction "P0[21]/RI1/RD1_G8") (pintype "bidirectional+no_connect"))
    )
    (net (code "76") (name "unconnected-(U2A-P0[22]{slash}RTS1{slash}TD1-PadH10)") (class "Default")
      (node (ref "U2") (pin "H10") (pinfunction "P0[22]/RTS1/TD1_H10") (pintype "bidirectional+no_connect"))
    )
    (net (code "77") (name "unconnected-(U2A-P0[23]{slash}AD0[0]{slash}I2SRX_CLK{slash}CAP3[0]-PadE5)") (class "Default")
      (node (ref "U2") (pin "E5") (pinfunction "P0[23]/AD0[0]/I2SRX_CLK/CAP3[0]_E5") (pintype "bidirectional+no_connect"))
    )
    (net (code "78") (name "unconnected-(U2A-P0[24]{slash}AD0[1]{slash}I2SRX_WS{slash}CAP3[1]-PadD1)") (class "Default")
      (node (ref "U2") (pin "D1") (pinfunction "P0[24]/AD0[1]/I2SRX_WS/CAP3[1]_D1") (pintype "bidirectional+no_connect"))
    )
    (net (code "79") (name "unconnected-(U2A-P0[25]{slash}AD0[2]{slash}I2SRX_SDA{slash}TXD3-PadD2)") (class "Default")
      (node (ref "U2") (pin "D2") (pinfunction "P0[25]/AD0[2]/I2SRX_SDA/TXD3_D2") (pintype "bidirectional+no_connect"))
    )
    (net (code "80") (name "unconnected-(U2A-P0[26]{slash}AD0[3]{slash}AOUT{slash}RXD3-PadD3)") (class "Default")
      (node (ref "U2") (pin "D3") (pinfunction "P0[26]/AD0[3]/AOUT/RXD3_D3") (pintype "bidirectional+no_connect"))
    )
    (net (code "81") (name "unconnected-(U2A-P0[27]{slash}SDA0{slash}USB_SDA-PadJ2)") (class "Default")
      (node (ref "U2") (pin "J2") (pinfunction "P0[27]/SDA0/USB_SDA_J2") (pintype "bidirectional+no_connect"))
    )
    (net (code "82") (name "unconnected-(U2A-P0[28]{slash}SCL0{slash}USB_SCL-PadJ1)") (class "Default")
      (node (ref "U2") (pin "J1") (pinfunction "P0[28]/SCL0/USB_SCL_J1") (pintype "bidirectional+no_connect"))
    )
    (net (code "83") (name "unconnected-(U2A-P0[29]{slash}USB_D+-PadJ3)") (class "Default")
      (node (ref "U2") (pin "J3") (pinfunction "P0[29]/USB_D+_J3") (pintype "bidirectional+no_connect"))
    )
    (net (code "84") (name "unconnected-(U2A-P0[30]{slash}USB_D--PadG4)") (class "Default")
      (node (ref "U2") (pin "G4") (pinfunction "P0[30]/USB_D-_G4") (pintype "bidirectional+no_connect"))
    )
    (net (code "85") (name "unconnected-(U2A-P1[0]{slash}ENET_TXD0-PadD5)") (class "Default")
      (node (ref "U2") (pin "D5") (pinfunction "P1[0]/ENET_TXD0_D5") (pintype "bidirectional+no_connect"))
    )
    (net (code "86") (name "unconnected-(U2A-P1[1]{slash}ENET_TXD1-PadB4)") (class "Default")
      (node (ref "U2") (pin "B4") (pinfunction "P1[1]/ENET_TXD1_B4") (pintype "bidirectional+no_connect"))
    )
    (net (code "87") (name "unconnected-(U2A-P1[4]{slash}ENET_TX_EN-PadA4)") (class "Default")
      (node (ref "U2") (pin "A4") (pinfunction "P1[4]/ENET_TX_EN_A4") (pintype "bidirectional+no_connect"))
    )
    (net (code "88") (name "unconnected-(U2A-P1[8]{slash}ENET_CRS-PadC5)") (class "Default")
      (node (ref "U2") (pin "C5") (pinfunction "P1[8]/ENET_CRS_C5") (pintype "bidirectional+no_connect"))
    )
    (net (code "89") (name "unconnected-(U2A-P1[9]{slash}ENET_RXD0-PadB5)") (class "Default")
      (node (ref "U2") (pin "B5") (pinfunction "P1[9]/ENET_RXD0_B5") (pintype "bidirectional+no_connect"))
    )
    (net (code "90") (name "unconnected-(U2A-P1[10]{slash}ENET_RXD1-PadA5)") (class "Default")
      (node (ref "U2") (pin "A5") (pinfunction "P1[10]/ENET_RXD1_A5") (pintype "bidirectional+no_connect"))
    )
    (net (code "91") (name "unconnected-(U2A-P1[14]{slash}ENET_RX_ER-PadD6)") (class "Default")
      (node (ref "U2") (pin "D6") (pinfunction "P1[14]/ENET_RX_ER_D6") (pintype "bidirectional+no_connect"))
    )
    (net (code "92") (name "unconnected-(U2A-P1[15]{slash}ENET_REF_CLK-PadC6)") (class "Default")
      (node (ref "U2") (pin "C6") (pinfunction "P1[15]/ENET_REF_CLK_C6") (pintype "bidirectional+no_connect"))
    )
    (net (code "93") (name "unconnected-(U2A-P1[16]{slash}ENET_MDC-PadA6)") (class "Default")
      (node (ref "U2") (pin "A6") (pinfunction "P1[16]/ENET_MDC_A6") (pintype "bidirectional+no_connect"))
    )
    (net (code "94") (name "unconnected-(U2A-P1[17]{slash}ENET_MDIO-PadB6)") (class "Default")
      (node (ref "U2") (pin "B6") (pinfunction "P1[17]/ENET_MDIO_B6") (pintype "bidirectional+no_connect"))
    )
    (net (code "95") (name "unconnected-(U2A-P1[18]{slash}USB_UP_LED{slash}PWM1[1]{slash}CAP1[0]-PadH4)") (class "Default")
      (node (ref "U2") (pin "H4") (pinfunction "P1[18]/USB_UP_LED/PWM1[1]/CAP1[0]_H4") (pintype "bidirectional+no_connect"))
    )
    (net (code "96") (name "unconnected-(U2A-P1[19]{slash}MCOA0{slash}~{USB_PPWR}{slash}CAP1[1]-PadJ4)") (class "Default")
      (node (ref "U2") (pin "J4") (pinfunction "P1[19]/MCOA0/~{USB_PPWR}/CAP1[1]_J4") (pintype "bidirectional+no_connect"))
    )
    (net (code "97") (name "unconnected-(U2A-P1[20]{slash}MCI0{slash}PWM1[2]{slash}SCK0-PadK4)") (class "Default")
      (node (ref "U2") (pin "K4") (pinfunction "P1[20]/MCI0/PWM1[2]/SCK0_K4") (pintype "bidirectional+no_connect"))
    )
    (net (code "98") (name "unconnected-(U2A-P1[21]{slash}~{MCABORT}{slash}PWM1[3]{slash}SSEL0-PadF5)") (class "Default")
      (node (ref "U2") (pin "F5") (pinfunction "P1[21]/~{MCABORT}/PWM1[3]/SSEL0_F5") (pintype "bidirectional+no_connect"))
    )
    (net (code "99") (name "unconnected-(U2A-P1[22]{slash}MCOB0{slash}USB_PWRD{slash}MAT1[0]-PadJ5)") (class "Default")
      (node (ref "U2") (pin "J5") (pinfunction "P1[22]/MCOB0/USB_PWRD/MAT1[0]_J5") (pintype "bidirectional+no_connect"))
    )
    (net (code "100") (name "unconnected-(U2A-P1[23]{slash}MCI1{slash}PWM1[4]{slash}MISO0-PadK5)") (class "Default")
      (node (ref "U2") (pin "K5") (pinfunction "P1[23]/MCI1/PWM1[4]/MISO0_K5") (pintype "bidirectional+no_connect"))
    )
    (net (code "101") (name "unconnected-(U2A-P1[24]{slash}MCI2{slash}PWM1[5]{slash}MOSI0-PadH5)") (class "Default")
      (node (ref "U2") (pin "H5") (pinfunction "P1[24]/MCI2/PWM1[5]/MOSI0_H5") (pintype "bidirectional+no_connect"))
    )
    (net (code "102") (name "unconnected-(U2A-P1[25]{slash}MCOA1{slash}MAT1[1]-PadG5)") (class "Default")
      (node (ref "U2") (pin "G5") (pinfunction "P1[25]/MCOA1/MAT1[1]_G5") (pintype "bidirectional+no_connect"))
    )
    (net (code "103") (name "unconnected-(U2A-P1[26]{slash}MCOB1{slash}PWM1[6]{slash}CAP0[0]-PadK6)") (class "Default")
      (node (ref "U2") (pin "K6") (pinfunction "P1[26]/MCOB1/PWM1[6]/CAP0[0]_K6") (pintype "bidirectional+no_connect"))
    )
    (net (code "104") (name "unconnected-(U2A-P1[27]{slash}CLKOUT{slash}~{USB_OVRCR}{slash}CAP0[1]-PadK7)") (class "Default")
      (node (ref "U2") (pin "K7") (pinfunction "P1[27]/CLKOUT/~{USB_OVRCR}/CAP0[1]_K7") (pintype "bidirectional+no_connect"))
    )
    (net (code "105") (name "unconnected-(U2A-P1[28]{slash}MCOA2{slash}PCAP1[0]{slash}MAT0[0]-PadJ7)") (class "Default")
      (node (ref "U2") (pin "J7") (pinfunction "P1[28]/MCOA2/PCAP1[0]/MAT0[0]_J7") (pintype "bidirectional+no_connect"))
    )
    (net (code "106") (name "unconnected-(U2A-P1[29]{slash}MCOB2{slash}PCAP1[1]{slash}MAT0[1]-PadG6)") (class "Default")
      (node (ref "U2") (pin "G6") (pinfunction "P1[29]/MCOB2/PCAP1[1]/MAT0[1]_G6") (pintype "bidirectional+no_connect"))
    )
    (net (code "107") (name "unconnected-(U2A-P1[30]{slash}VBUS{slash}AD0[4]-PadH1)") (class "Default")
      (node (ref "U2") (pin "H1") (pinfunction "P1[30]/VBUS/AD0[4]_H1") (pintype "bidirectional+no_connect"))
    )
    (net (code "108") (name "unconnected-(U2A-P2[0]{slash}PWM1[1]{slash}TXD1-PadB9)") (class "Default")
      (node (ref "U2") (pin "B9") (pinfunction "P2[0]/PWM1[1]/TXD1_B9") (pintype "bidirectional+no_connect"))
    )
    (net (code "109") (name "unconnected-(U2A-P2[1]{slash}PWM1[2]{slash}RXD1-PadB10)") (class "Default")
      (node (ref "U2") (pin "B10") (pinfunction "P2[1]/PWM1[2]/RXD1_B10") (pintype "bidirectional+no_connect"))
    )
    (net (code "110") (name "unconnected-(U2A-P2[2]{slash}PWM1[3]{slash}CTS1{slash}TRACEDATA[3]-PadD8)") (class "Default")
      (node (ref "U2") (pin "D8") (pinfunction "P2[2]/PWM1[3]/CTS1/TRACEDATA[3]_D8") (pintype "bidirectional+no_connect"))
    )
    (net (code "111") (name "unconnected-(U2A-P2[3]{slash}PWM1[4]{slash}DCD1{slash}TRACEDATA[2]-PadE7)") (class "Default")
      (node (ref "U2") (pin "E7") (pinfunction "P2[3]/PWM1[4]/DCD1/TRACEDATA[2]_E7") (pintype "bidirectional+no_connect"))
    )
    (net (code "112") (name "unconnected-(U2A-P2[4]{slash}PWM1[5]{slash}DSR1{slash}TRACEDATA[1]-PadD9)") (class "Default")
      (node (ref "U2") (pin "D9") (pinfunction "P2[4]/PWM1[5]/DSR1/TRACEDATA[1]_D9") (pintype "bidirectional+no_connect"))
    )
    (net (code "113") (name "unconnected-(U2A-P2[5]{slash}PWM1[6]{slash}DTR1{slash}TRACEDATA[0]-PadD10)") (class "Default")
      (node (ref "U2") (pin "D10") (pinfunction "P2[5]/PWM1[6]/DTR1/TRACEDATA[0]_D10") (pintype "bidirectional+no_connect"))
    )
    (net (code "114") (name "unconnected-(U2A-P2[6]{slash}PCAP1[0]{slash}RI1{slash}TRACECLK-PadE8)") (class "Default")
      (node (ref "U2") (pin "E8") (pinfunction "P2[6]/PCAP1[0]/RI1/TRACECLK_E8") (pintype "bidirectional+no_connect"))
    )
    (net (code "115") (name "unconnected-(U2A-P2[7]{slash}RD2{slash}RTS1-PadE9)") (class "Default")
      (node (ref "U2") (pin "E9") (pinfunction "P2[7]/RD2/RTS1_E9") (pintype "bidirectional+no_connect"))
    )
    (net (code "116") (name "unconnected-(U2A-P2[8]{slash}TD2{slash}TXD2-PadE10)") (class "Default")
      (node (ref "U2") (pin "E10") (pinfunction "P2[8]/TD2/TXD2_E10") (pintype "bidirectional+no_connect"))
    )
    (net (code "117") (name "unconnected-(U2A-P2[9]{slash}USB_CONNECT{slash}RXD2-PadF7)") (class "Default")
      (node (ref "U2") (pin "F7") (pinfunction "P2[9]/USB_CONNECT/RXD2_F7") (pintype "bidirectional+no_connect"))
    )
    (net (code "118") (name "unconnected-(U2A-P2[10]{slash}~{EINT0}{slash}NMI-PadJ10)") (class "Default")
      (node (ref "U2") (pin "J10") (pinfunction "P2[10]/~{EINT0}/NMI_J10") (pintype "bidirectional+no_connect"))
    )
    (net (code "119") (name "unconnected-(U2A-P2[11]{slash}~{EINT1}{slash}I2STX_CLK-PadH8)") (class "Default")
      (node (ref "U2") (pin "H8") (pinfunction "P2[11]/~{EINT1}/I2STX_CLK_H8") (pintype "bidirectional+no_connect"))
    )
    (net (code "120") (name "unconnected-(U2A-P2[12]{slash}~{EINT2}{slash}I2STX_WS-PadK10)") (class "Default")
      (node (ref "U2") (pin "K10") (pinfunction "P2[12]/~{EINT2}/I2STX_WS_K10") (pintype "bidirectional+no_connect"))
    )
    (net (code "121") (name "unconnected-(U2A-P2[13]{slash}~{EINT3}{slash}I2STX_SDA-PadJ9)") (class "Default")
      (node (ref "U2") (pin "J9") (pinfunction "P2[13]/~{EINT3}/I2STX_SDA_J9") (pintype "bidirectional+no_connect"))
    )
    (net (code "122") (name "unconnected-(U2A-P3[25]{slash}MAT0[0]{slash}PWM1[2]-PadH3)") (class "Default")
      (node (ref "U2") (pin "H3") (pinfunction "P3[25]/MAT0[0]/PWM1[2]_H3") (pintype "bidirectional+no_connect"))
    )
    (net (code "123") (name "unconnected-(U2A-P3[26]{slash}STCLK{slash}MAT0[1]{slash}PWM1[3]-PadK1)") (class "Default")
      (node (ref "U2") (pin "K1") (pinfunction "P3[26]/STCLK/MAT0[1]/PWM1[3]_K1") (pintype "bidirectional+no_connect"))
    )
    (net (code "124") (name "unconnected-(U2A-P4[28]{slash}RX_MCLK{slash}MAT2[0]{slash}TXD3-PadC7)") (class "Default")
      (node (ref "U2") (pin "C7") (pinfunction "P4[28]/RX_MCLK/MAT2[0]/TXD3_C7") (pintype "bidirectional+no_connect"))
    )
    (net (code "125") (name "unconnected-(U2A-P4[29]{slash}TX_MCLK{slash}MAT2[1]{slash}RXD3-PadE6)") (class "Default")
      (node (ref "U2") (pin "E6") (pinfunction "P4[29]/TX_MCLK/MAT2[1]/RXD3_E6") (pintype "bidirectional+no_connect"))
    )
    (net (code "126") (name "unconnected-(U2A-RTCK-PadB2)") (class "Default")
      (node (ref "U2") (pin "B2") (pinfunction "RTCK_B2") (pintype "output+no_connect"))
    )
    (net (code "127") (name "unconnected-(U2A-TCK{slash}SWDCLK-PadC1)") (class "Default")
      (node (ref "U2") (pin "C1") (pinfunction "TCK/SWDCLK_C1") (pintype "input+no_connect"))
    )
    (net (code "128") (name "unconnected-(U2A-TDI-PadC3)") (class "Default")
      (node (ref "U2") (pin "C3") (pinfunction "TDI_C3") (pintype "input+no_connect"))
    )
    (net (code "129") (name "unconnected-(U2A-TDO{slash}SWO-PadA1)") (class "Default")
      (node (ref "U2") (pin "A1") (pinfunction "TDO/SWO_A1") (pintype "output+no_connect"))
    )
    (net (code "130") (name "unconnected-(U2A-TMS{slash}SWDIO-PadB1)") (class "Default")
      (node (ref "U2") (pin "B1") (pinfunction "TMS/SWDIO_B1") (pintype "bidirectional+no_connect"))
    )
    (net (code "131") (name "unconnected-(U2A-XTAL2-PadG3)") (class "Default")
      (node (ref "U2") (pin "G3") (pinfunction "XTAL2_G3") (pintype "passive+no_connect"))
    )
    (net (code "132") (name "unconnected-(U2A-~{RESET}-PadF3)") (class "Default")
      (node (ref "U2") (pin "F3") (pinfunction "~{RESET}_F3") (pintype "input+no_connect"))
    )
    (net (code "133") (name "unconnected-(U2A-~{TRST}-PadC2)") (class "Default")
      (node (ref "U2") (pin "C2") (pinfunction "~{TRST}_C2") (pintype "input+no_connect"))
    )
    (net (code "134") (name "unconnected-(X1-STAND-BY-Pad1)") (class "Default")
      (node (ref "X1") (pin "1") (pinfunction "STAND-BY_1") (pintype "input+no_connect"))
    )
  )
)
